# transponder_2018_v2.net
KiCad netlist of a schematic drawn in EAGLE
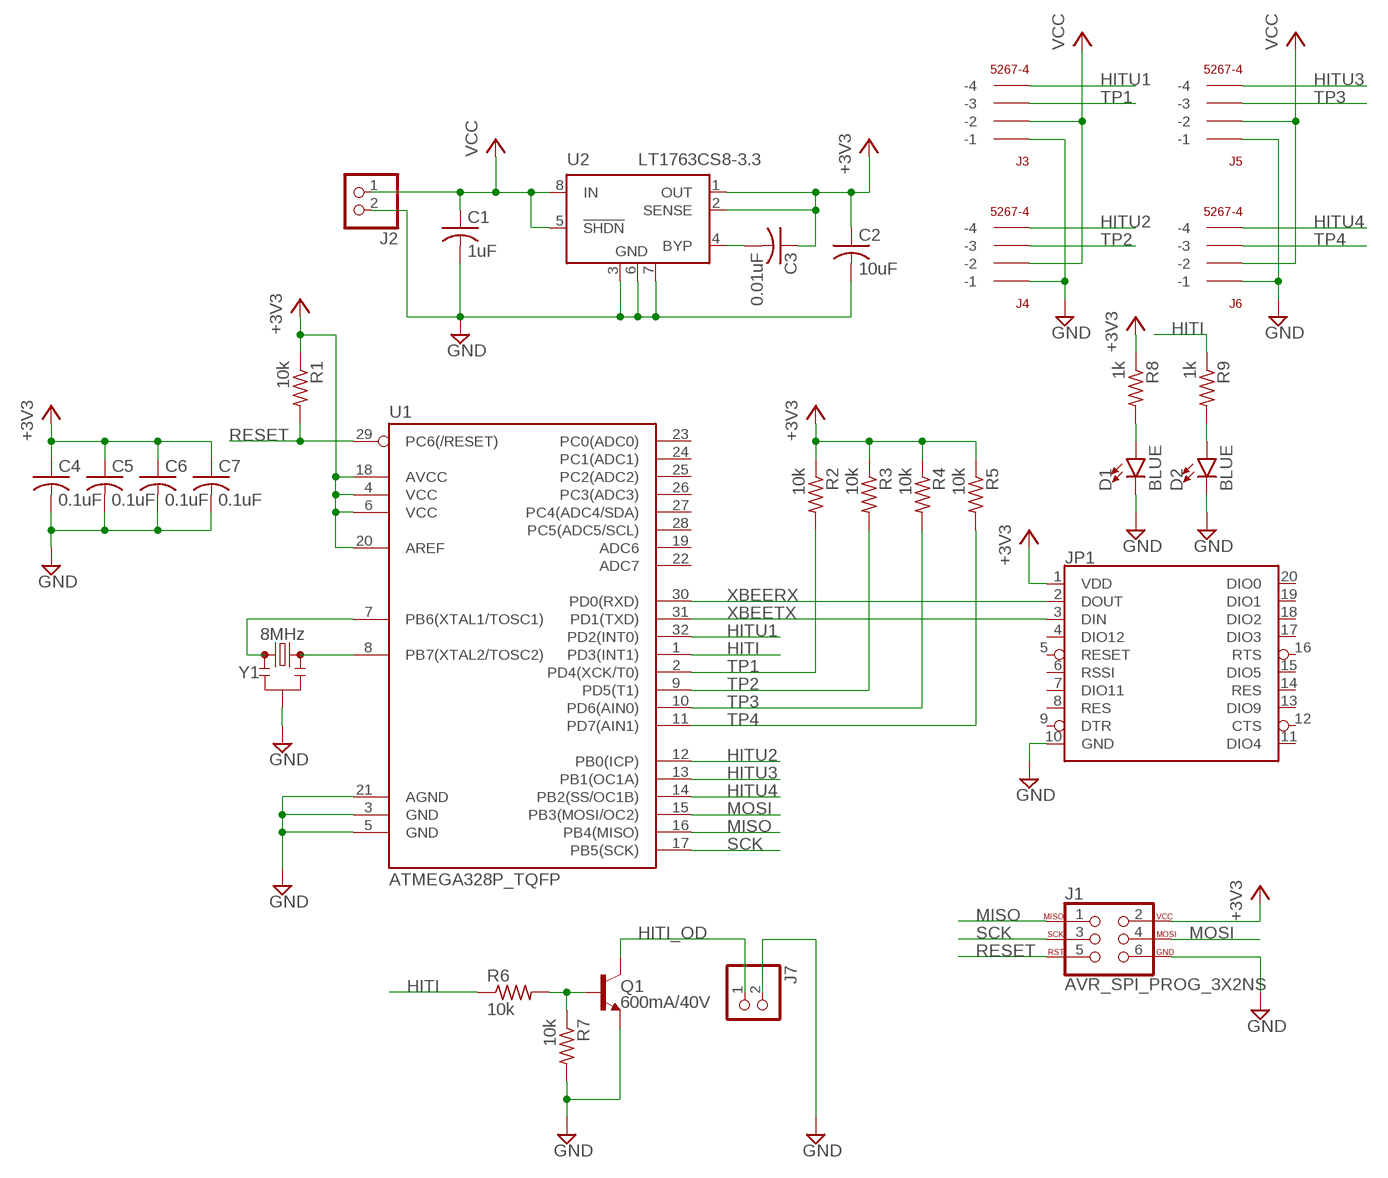
[diagram p0: schematic, sheet 1]

(export (version "E")
  (design (tool "Eeschema 10.0.6"))
  (components
    (comp (ref "C1")
      (value "1uF")
      (footprint "eagle-import:C0603")
      (libsource (lib "eagle-import") (part "C-USC0603"))
    )
    (comp (ref "C2")
      (value "10uF")
      (footprint "eagle-import:C1206")
      (libsource (lib "eagle-import") (part "C-USC1206"))
    )
    (comp (ref "C3")
      (value "0.01uF")
      (footprint "eagle-import:C0603")
      (libsource (lib "eagle-import") (part "C-USC0603"))
    )
    (comp (ref "C4")
      (value "0.1uF")
      (footprint "eagle-import:C0603")
      (libsource (lib "eagle-import") (part "C-USC0603"))
    )
    (comp (ref "C5")
      (value "0.1uF")
      (footprint "eagle-import:C0603")
      (libsource (lib "eagle-import") (part "C-USC0603"))
    )
    (comp (ref "C6")
      (value "0.1uF")
      (footprint "eagle-import:C0603")
      (libsource (lib "eagle-import") (part "C-USC0603"))
    )
    (comp (ref "C7")
      (value "0.1uF")
      (footprint "eagle-import:C0603")
      (libsource (lib "eagle-import") (part "C-USC0603"))
    )
    (comp (ref "D1")
      (value "BLUE")
      (footprint "eagle-import:LED-0603")
      (libsource (lib "eagle-import") (part "LED-BLUE0603"))
    )
    (comp (ref "D2")
      (value "BLUE")
      (footprint "eagle-import:LED-0603")
      (libsource (lib "eagle-import") (part "LED-BLUE0603"))
    )
    (comp (ref "J1")
      (value "AVR_SPI_PROG_3X2NS")
      (footprint "eagle-import:2X3-NS")
      (libsource (lib "eagle-import") (part "AVR_SPI_PROG_3X2NS"))
    )
    (comp (ref "J2")
      (value "JST_2PIN-THM-RA")
      (footprint "eagle-import:JST-PH-2-THM-RA")
      (libsource (lib "eagle-import") (part "JST_2PIN-THM-RA"))
    )
    (comp (ref "J3")
      (value "5267-4")
      (footprint "eagle-import:5267-4")
      (libsource (lib "eagle-import") (part "5267-4"))
    )
    (comp (ref "J4")
      (value "5267-4")
      (footprint "eagle-import:5267-4")
      (libsource (lib "eagle-import") (part "5267-4"))
    )
    (comp (ref "J5")
      (value "5267-4")
      (footprint "eagle-import:5267-4")
      (libsource (lib "eagle-import") (part "5267-4"))
    )
    (comp (ref "J6")
      (value "5267-4")
      (footprint "eagle-import:5267-4")
      (libsource (lib "eagle-import") (part "5267-4"))
    )
    (comp (ref "J7")
      (value "JST_2PIN-THM-RA")
      (footprint "eagle-import:JST-PH-2-THM-RA")
      (libsource (lib "eagle-import") (part "JST_2PIN-THM-RA"))
    )
    (comp (ref "JP1")
      (value "XBEESMD")
      (footprint "eagle-import:XBEE-SMD")
      (libsource (lib "eagle-import") (part "XBEESMD"))
    )
    (comp (ref "Q1")
      (value "600mA/40V")
      (footprint "eagle-import:SOT23-3")
      (libsource (lib "eagle-import") (part "TRANS_NPN-MMBT2222AL"))
    )
    (comp (ref "R1")
      (value "10k")
      (footprint "eagle-import:R0603")
      (libsource (lib "eagle-import") (part "R-US_R0603"))
    )
    (comp (ref "R2")
      (value "10k")
      (footprint "eagle-import:R0603")
      (libsource (lib "eagle-import") (part "R-US_R0603"))
    )
    (comp (ref "R3")
      (value "10k")
      (footprint "eagle-import:R0603")
      (libsource (lib "eagle-import") (part "R-US_R0603"))
    )
    (comp (ref "R4")
      (value "10k")
      (footprint "eagle-import:R0603")
      (libsource (lib "eagle-import") (part "R-US_R0603"))
    )
    (comp (ref "R5")
      (value "10k")
      (footprint "eagle-import:R0603")
      (libsource (lib "eagle-import") (part "R-US_R0603"))
    )
    (comp (ref "R6")
      (value "10k")
      (footprint "eagle-import:R0603")
      (libsource (lib "eagle-import") (part "R-US_R0603"))
    )
    (comp (ref "R7")
      (value "10k")
      (footprint "eagle-import:R0603")
      (libsource (lib "eagle-import") (part "R-US_R0603"))
    )
    (comp (ref "R8")
      (value "1k")
      (footprint "eagle-import:R0603")
      (libsource (lib "eagle-import") (part "R-US_R0603"))
    )
    (comp (ref "R9")
      (value "1k")
      (footprint "eagle-import:R0603")
      (libsource (lib "eagle-import") (part "R-US_R0603"))
    )
    (comp (ref "U1")
      (value "ATMEGA328P_TQFP")
      (footprint "eagle-import:TQFP32-08")
      (libsource (lib "eagle-import") (part "ATMEGA328P_TQFP"))
    )
    (comp (ref "U2")
      (value "LT1763CS8-3.3")
      (footprint "eagle-import:SOIC8")
      (libsource (lib "eagle-import") (part "LT1763CS8-3.3"))
    )
    (comp (ref "Y1")
      (value "8MHz")
      (footprint "eagle-import:RESONATOR-SMD-3.2X1.3")
      (libsource (lib "eagle-import") (part "RESONATOR-8MHZSMD_3.2X1.3"))
    )
  )
  (nets
    (net (code "1") (name "+3V3") (class "Default")
      (node (ref "C2") (pin "1") (pinfunction "1_1") (pintype "passive"))
      (node (ref "C3") (pin "1") (pinfunction "1_1") (pintype "passive"))
      (node (ref "C4") (pin "1") (pinfunction "1_1") (pintype "passive"))
      (node (ref "C5") (pin "1") (pinfunction "1_1") (pintype "passive"))
      (node (ref "C6") (pin "1") (pinfunction "1_1") (pintype "passive"))
      (node (ref "C7") (pin "1") (pinfunction "1_1") (pintype "passive"))
      (node (ref "J1") (pin "2") (pinfunction "2_2") (pintype "passive"))
      (node (ref "JP1") (pin "1") (pinfunction "VDD_1") (pintype "power_in"))
      (node (ref "R1") (pin "1") (pinfunction "1_1") (pintype "passive"))
      (node (ref "R2") (pin "1") (pinfunction "1_1") (pintype "passive"))
      (node (ref "R3") (pin "1") (pinfunction "1_1") (pintype "passive"))
      (node (ref "R4") (pin "1") (pinfunction "1_1") (pintype "passive"))
      (node (ref "R5") (pin "1") (pinfunction "1_1") (pintype "passive"))
      (node (ref "R8") (pin "1") (pinfunction "1_1") (pintype "passive"))
      (node (ref "U1") (pin "18") (pinfunction "AVCC_18") (pintype "bidirectional"))
      (node (ref "U1") (pin "20") (pinfunction "AREF_20") (pintype "bidirectional"))
      (node (ref "U1") (pin "4") (pinfunction "VCC_4") (pintype "bidirectional"))
      (node (ref "U1") (pin "6") (pinfunction "VCC_6") (pintype "bidirectional"))
      (node (ref "U2") (pin "1") (pinfunction "OUT_1") (pintype "passive"))
      (node (ref "U2") (pin "2") (pinfunction "SENSE_2") (pintype "input"))
    )
    (net (code "2") (name "/HITI") (class "Default")
      (node (ref "R6") (pin "1") (pinfunction "1_1") (pintype "passive"))
      (node (ref "R9") (pin "1") (pinfunction "1_1") (pintype "passive"))
      (node (ref "U1") (pin "1") (pinfunction "PD3(INT1)_1") (pintype "bidirectional"))
    )
    (net (code "3") (name "/HITI_OD") (class "Default")
      (node (ref "J7") (pin "1") (pinfunction "2_1") (pintype "passive"))
      (node (ref "Q1") (pin "3") (pinfunction "C_3") (pintype "passive"))
    )
    (net (code "4") (name "/HITU1") (class "Default")
      (node (ref "J3") (pin "P$4") (pinfunction "-4_P$4") (pintype "bidirectional"))
      (node (ref "U1") (pin "32") (pinfunction "PD2(INT0)_32") (pintype "bidirectional"))
    )
    (net (code "5") (name "/HITU2") (class "Default")
      (node (ref "J4") (pin "P$4") (pinfunction "-4_P$4") (pintype "bidirectional"))
      (node (ref "U1") (pin "12") (pinfunction "PB0(ICP)_12") (pintype "bidirectional"))
    )
    (net (code "6") (name "/HITU3") (class "Default")
      (node (ref "J5") (pin "P$4") (pinfunction "-4_P$4") (pintype "bidirectional"))
      (node (ref "U1") (pin "13") (pinfunction "PB1(OC1A)_13") (pintype "bidirectional"))
    )
    (net (code "7") (name "/HITU4") (class "Default")
      (node (ref "J6") (pin "P$4") (pinfunction "-4_P$4") (pintype "bidirectional"))
      (node (ref "U1") (pin "14") (pinfunction "PB2(SS/OC1B)_14") (pintype "bidirectional"))
    )
    (net (code "8") (name "/MISO") (class "Default")
      (node (ref "J1") (pin "1") (pinfunction "1_1") (pintype "passive"))
      (node (ref "U1") (pin "16") (pinfunction "PB4(MISO)_16") (pintype "bidirectional"))
    )
    (net (code "9") (name "/MOSI") (class "Default")
      (node (ref "J1") (pin "4") (pinfunction "4_4") (pintype "passive"))
      (node (ref "U1") (pin "15") (pinfunction "PB3(MOSI/OC2)_15") (pintype "bidirectional"))
    )
    (net (code "10") (name "/RESET") (class "Default")
      (node (ref "J1") (pin "5") (pinfunction "5_5") (pintype "passive"))
      (node (ref "R1") (pin "2") (pinfunction "2_2") (pintype "passive"))
      (node (ref "U1") (pin "29") (pinfunction "PC6(/RESET)_29") (pintype "bidirectional"))
    )
    (net (code "11") (name "/SCK") (class "Default")
      (node (ref "J1") (pin "3") (pinfunction "3_3") (pintype "passive"))
      (node (ref "U1") (pin "17") (pinfunction "PB5(SCK)_17") (pintype "bidirectional"))
    )
    (net (code "12") (name "/TP1") (class "Default")
      (node (ref "J3") (pin "P$3") (pinfunction "-3_P$3") (pintype "bidirectional"))
      (node (ref "R2") (pin "2") (pinfunction "2_2") (pintype "passive"))
      (node (ref "U1") (pin "2") (pinfunction "PD4(XCK/T0)_2") (pintype "bidirectional"))
    )
    (net (code "13") (name "/TP2") (class "Default")
      (node (ref "J4") (pin "P$3") (pinfunction "-3_P$3") (pintype "bidirectional"))
      (node (ref "R3") (pin "2") (pinfunction "2_2") (pintype "passive"))
      (node (ref "U1") (pin "9") (pinfunction "PD5(T1)_9") (pintype "bidirectional"))
    )
    (net (code "14") (name "/TP3") (class "Default")
      (node (ref "J5") (pin "P$3") (pinfunction "-3_P$3") (pintype "bidirectional"))
      (node (ref "R4") (pin "2") (pinfunction "2_2") (pintype "passive"))
      (node (ref "U1") (pin "10") (pinfunction "PD6(AIN0)_10") (pintype "bidirectional"))
    )
    (net (code "15") (name "/TP4") (class "Default")
      (node (ref "J6") (pin "P$3") (pinfunction "-3_P$3") (pintype "bidirectional"))
      (node (ref "R5") (pin "2") (pinfunction "2_2") (pintype "passive"))
      (node (ref "U1") (pin "11") (pinfunction "PD7(AIN1)_11") (pintype "bidirectional"))
    )
    (net (code "16") (name "/XBEERX") (class "Default")
      (node (ref "JP1") (pin "2") (pinfunction "DOUT_2") (pintype "output"))
      (node (ref "U1") (pin "30") (pinfunction "PD0(RXD)_30") (pintype "bidirectional"))
    )
    (net (code "17") (name "/XBEETX") (class "Default")
      (node (ref "JP1") (pin "3") (pinfunction "DIN_3") (pintype "input"))
      (node (ref "U1") (pin "31") (pinfunction "PD1(TXD)_31") (pintype "bidirectional"))
    )
    (net (code "18") (name "GND") (class "Default")
      (node (ref "C1") (pin "2") (pinfunction "2_2") (pintype "passive"))
      (node (ref "C2") (pin "2") (pinfunction "2_2") (pintype "passive"))
      (node (ref "C4") (pin "2") (pinfunction "2_2") (pintype "passive"))
      (node (ref "C5") (pin "2") (pinfunction "2_2") (pintype "passive"))
      (node (ref "C6") (pin "2") (pinfunction "2_2") (pintype "passive"))
      (node (ref "C7") (pin "2") (pinfunction "2_2") (pintype "passive"))
      (node (ref "D1") (pin "C") (pinfunction "C_C") (pintype "passive"))
      (node (ref "D2") (pin "C") (pinfunction "C_C") (pintype "passive"))
      (node (ref "J1") (pin "6") (pinfunction "6_6") (pintype "passive"))
      (node (ref "J2") (pin "2") (pinfunction "1_2") (pintype "passive"))
      (node (ref "J3") (pin "P$1") (pinfunction "-1_P$1") (pintype "bidirectional"))
      (node (ref "J4") (pin "P$1") (pinfunction "-1_P$1") (pintype "bidirectional"))
      (node (ref "J5") (pin "P$1") (pinfunction "-1_P$1") (pintype "bidirectional"))
      (node (ref "J6") (pin "P$1") (pinfunction "-1_P$1") (pintype "bidirectional"))
      (node (ref "J7") (pin "2") (pinfunction "1_2") (pintype "passive"))
      (node (ref "JP1") (pin "10") (pinfunction "GND_10") (pintype "power_in"))
      (node (ref "Q1") (pin "2") (pinfunction "E_2") (pintype "passive"))
      (node (ref "R7") (pin "2") (pinfunction "2_2") (pintype "passive"))
      (node (ref "U1") (pin "21") (pinfunction "AGND_21") (pintype "bidirectional"))
      (node (ref "U1") (pin "3") (pinfunction "GND_3") (pintype "bidirectional"))
      (node (ref "U1") (pin "5") (pinfunction "GND_5") (pintype "bidirectional"))
      (node (ref "U2") (pin "3") (pinfunction "GND_3") (pintype "power_in"))
      (node (ref "U2") (pin "6") (pinfunction "GND_6") (pintype "power_in"))
      (node (ref "U2") (pin "7") (pinfunction "GND_7") (pintype "power_in"))
      (node (ref "Y1") (pin "2") (pinfunction "2_2") (pintype "passive"))
    )
    (net (code "19") (name "Net-(D1-PadA)") (class "Default")
      (node (ref "D1") (pin "A") (pinfunction "A_A") (pintype "passive"))
      (node (ref "R8") (pin "2") (pinfunction "2_2") (pintype "passive"))
    )
    (net (code "20") (name "Net-(D2-PadA)") (class "Default")
      (node (ref "D2") (pin "A") (pinfunction "A_A") (pintype "passive"))
      (node (ref "R9") (pin "2") (pinfunction "2_2") (pintype "passive"))
    )
    (net (code "21") (name "Net-(Q1-B)") (class "Default")
      (node (ref "Q1") (pin "1") (pinfunction "B_1") (pintype "passive"))
      (node (ref "R6") (pin "2") (pinfunction "2_2") (pintype "passive"))
      (node (ref "R7") (pin "1") (pinfunction "1_1") (pintype "passive"))
    )
    (net (code "22") (name "Net-(U1-PB6(XTAL1{slash}TOSC1))") (class "Default")
      (node (ref "U1") (pin "7") (pinfunction "PB6(XTAL1/TOSC1)_7") (pintype "bidirectional"))
      (node (ref "Y1") (pin "1") (pinfunction "1_1") (pintype "passive"))
    )
    (net (code "23") (name "Net-(U1-PB7(XTAL2{slash}TOSC2))") (class "Default")
      (node (ref "U1") (pin "8") (pinfunction "PB7(XTAL2/TOSC2)_8") (pintype "bidirectional"))
      (node (ref "Y1") (pin "3") (pinfunction "3_3") (pintype "passive"))
    )
    (net (code "24") (name "Net-(U2-BYP)") (class "Default")
      (node (ref "C3") (pin "2") (pinfunction "2_2") (pintype "passive"))
      (node (ref "U2") (pin "4") (pinfunction "BYP_4") (pintype "input"))
    )
    (net (code "25") (name "VCC") (class "Default")
      (node (ref "C1") (pin "1") (pinfunction "1_1") (pintype "passive"))
      (node (ref "J2") (pin "1") (pinfunction "2_1") (pintype "passive"))
      (node (ref "J3") (pin "P$2") (pinfunction "-2_P$2") (pintype "bidirectional"))
      (node (ref "J4") (pin "P$2") (pinfunction "-2_P$2") (pintype "bidirectional"))
      (node (ref "J5") (pin "P$2") (pinfunction "-2_P$2") (pintype "bidirectional"))
      (node (ref "J6") (pin "P$2") (pinfunction "-2_P$2") (pintype "bidirectional"))
      (node (ref "U2") (pin "5") (pinfunction "~{SHDN}_5") (pintype "input"))
      (node (ref "U2") (pin "8") (pinfunction "IN_8") (pintype "input"))
    )
    (net (code "26") (name "unconnected-(JP1-CTS-Pad12)") (class "Default")
      (node (ref "JP1") (pin "12") (pinfunction "CTS_12") (pintype "output"))
    )
    (net (code "27") (name "unconnected-(JP1-DIO0-Pad20)") (class "Default")
      (node (ref "JP1") (pin "20") (pinfunction "DIO0_20") (pintype "bidirectional"))
    )
    (net (code "28") (name "unconnected-(JP1-DIO1-Pad19)") (class "Default")
      (node (ref "JP1") (pin "19") (pinfunction "DIO1_19") (pintype "bidirectional"))
    )
    (net (code "29") (name "unconnected-(JP1-DIO2-Pad18)") (class "Default")
      (node (ref "JP1") (pin "18") (pinfunction "DIO2_18") (pintype "bidirectional"))
    )
    (net (code "30") (name "unconnected-(JP1-DIO3-Pad17)") (class "Default")
      (node (ref "JP1") (pin "17") (pinfunction "DIO3_17") (pintype "bidirectional"))
    )
    (net (code "31") (name "unconnected-(JP1-DIO4-Pad11)") (class "Default")
      (node (ref "JP1") (pin "11") (pinfunction "DIO4_11") (pintype "bidirectional"))
    )
    (net (code "32") (name "unconnected-(JP1-DIO5-Pad15)") (class "Default")
      (node (ref "JP1") (pin "15") (pinfunction "DIO5_15") (pintype "bidirectional"))
    )
    (net (code "33") (name "unconnected-(JP1-DIO9-Pad13)") (class "Default")
      (node (ref "JP1") (pin "13") (pinfunction "DIO9_13") (pintype "bidirectional"))
    )
    (net (code "34") (name "unconnected-(JP1-DIO11-Pad7)") (class "Default")
      (node (ref "JP1") (pin "7") (pinfunction "DIO11_7") (pintype "bidirectional"))
    )
    (net (code "35") (name "unconnected-(JP1-DIO12-Pad4)") (class "Default")
      (node (ref "JP1") (pin "4") (pinfunction "DIO12_4") (pintype "bidirectional"))
    )
    (net (code "36") (name "unconnected-(JP1-DTR-Pad9)") (class "Default")
      (node (ref "JP1") (pin "9") (pinfunction "DTR_9") (pintype "bidirectional"))
    )
    (net (code "37") (name "unconnected-(JP1-RES-Pad8)") (class "Default")
      (node (ref "JP1") (pin "8") (pinfunction "RES_8") (pintype "bidirectional"))
    )
    (net (code "38") (name "unconnected-(JP1-RES-Pad14)") (class "Default")
      (node (ref "JP1") (pin "14") (pinfunction "RES_14") (pintype "bidirectional"))
    )
    (net (code "39") (name "unconnected-(JP1-RESET-Pad5)") (class "Default")
      (node (ref "JP1") (pin "5") (pinfunction "RESET_5") (pintype "input"))
    )
    (net (code "40") (name "unconnected-(JP1-RSSI-Pad6)") (class "Default")
      (node (ref "JP1") (pin "6") (pinfunction "RSSI_6") (pintype "bidirectional"))
    )
    (net (code "41") (name "unconnected-(JP1-RTS-Pad16)") (class "Default")
      (node (ref "JP1") (pin "16") (pinfunction "RTS_16") (pintype "input"))
    )
    (net (code "42") (name "unconnected-(U1-ADC6-Pad19)") (class "Default")
      (node (ref "U1") (pin "19") (pinfunction "ADC6_19") (pintype "bidirectional"))
    )
    (net (code "43") (name "unconnected-(U1-ADC7-Pad22)") (class "Default")
      (node (ref "U1") (pin "22") (pinfunction "ADC7_22") (pintype "bidirectional"))
    )
    (net (code "44") (name "unconnected-(U1-PC0(ADC0)-Pad23)") (class "Default")
      (node (ref "U1") (pin "23") (pinfunction "PC0(ADC0)_23") (pintype "bidirectional"))
    )
    (net (code "45") (name "unconnected-(U1-PC1(ADC1)-Pad24)") (class "Default")
      (node (ref "U1") (pin "24") (pinfunction "PC1(ADC1)_24") (pintype "bidirectional"))
    )
    (net (code "46") (name "unconnected-(U1-PC2(ADC2)-Pad25)") (class "Default")
      (node (ref "U1") (pin "25") (pinfunction "PC2(ADC2)_25") (pintype "bidirectional"))
    )
    (net (code "47") (name "unconnected-(U1-PC3(ADC3)-Pad26)") (class "Default")
      (node (ref "U1") (pin "26") (pinfunction "PC3(ADC3)_26") (pintype "bidirectional"))
    )
    (net (code "48") (name "unconnected-(U1-PC4(ADC4{slash}SDA)-Pad27)") (class "Default")
      (node (ref "U1") (pin "27") (pinfunction "PC4(ADC4/SDA)_27") (pintype "bidirectional"))
    )
    (net (code "49") (name "unconnected-(U1-PC5(ADC5{slash}SCL)-Pad28)") (class "Default")
      (node (ref "U1") (pin "28") (pinfunction "PC5(ADC5/SCL)_28") (pintype "bidirectional"))
    )
  )
)
